# Sch_Rele.net
KiCad netlist of a schematic drawn in Altium Designer
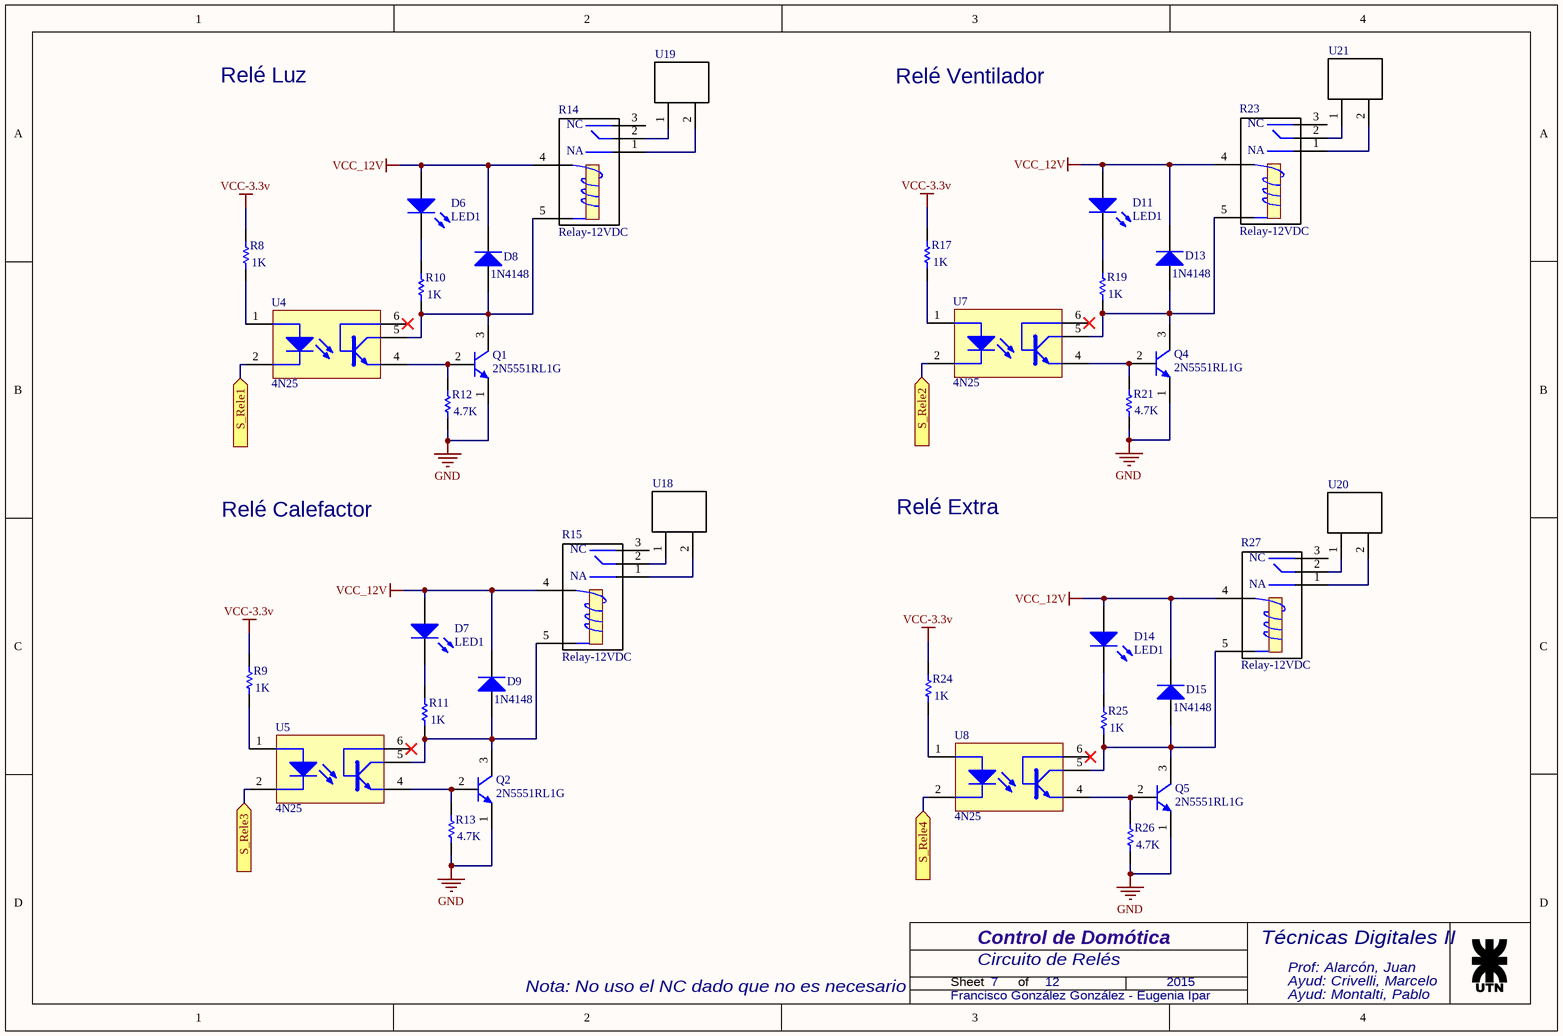
[diagram p0: Sch_Rele.SchDoc]

(export (version "E")
  (design (tool "Eeschema 10.0.6"))
  (components
    (comp (ref "D6")
      (value "LED1")
      (footprint "Type 3mm")
      (description "THT LED round mono-color color lens, WL-TMRW, Super Red")
      (fields (field (name "PARTNUMBER") "151031SS06000") (field (name "MANUFACTURER") "Wuerth Elektronik"))
      (libsource (lib "Altium Content Vault") (part "WE-LED_K1A2-2"))
    )
    (comp (ref "D7")
      (value "LED1")
      (footprint "Type 3mm")
      (description "THT LED round mono-color color lens, WL-TMRW, Super Red")
      (fields (field (name "PARTNUMBER") "151031SS06000") (field (name "MANUFACTURER") "Wuerth Elektronik"))
      (libsource (lib "Altium Content Vault") (part "WE-LED_K1A2-2"))
    )
    (comp (ref "D8")
      (value "1N4148")
      (footprint "DO-35")
      (description "High Conductance Fast Diode")
      (fields (field (name "PUBLISHER") "Altium Limited"))
      (libsource (lib "Miscellaneous Devices") (part "Diode 1N4148"))
    )
    (comp (ref "D9")
      (value "1N4148")
      (footprint "DO-35")
      (description "High Conductance Fast Diode")
      (fields (field (name "PUBLISHER") "Altium Limited"))
      (libsource (lib "Miscellaneous Devices") (part "Diode 1N4148"))
    )
    (comp (ref "D11")
      (value "LED1")
      (footprint "Type 3mm")
      (description "THT LED round mono-color color lens, WL-TMRW, Super Red")
      (fields (field (name "PARTNUMBER") "151031SS06000") (field (name "MANUFACTURER") "Wuerth Elektronik"))
      (libsource (lib "Altium Content Vault") (part "WE-LED_K1A2-2"))
    )
    (comp (ref "D13")
      (value "1N4148")
      (footprint "DO-35")
      (description "High Conductance Fast Diode")
      (fields (field (name "PUBLISHER") "Altium Limited"))
      (libsource (lib "Miscellaneous Devices") (part "Diode 1N4148"))
    )
    (comp (ref "D14")
      (value "LED1")
      (footprint "Type 3mm")
      (description "THT LED round mono-color color lens, WL-TMRW, Super Red")
      (fields (field (name "PARTNUMBER") "151031SS06000") (field (name "MANUFACTURER") "Wuerth Elektronik"))
      (libsource (lib "Altium Content Vault") (part "WE-LED_K1A2-2"))
    )
    (comp (ref "D15")
      (value "1N4148")
      (footprint "DO-35")
      (description "High Conductance Fast Diode")
      (fields (field (name "PUBLISHER") "Altium Limited"))
      (libsource (lib "Miscellaneous Devices") (part "Diode 1N4148"))
    )
    (comp (ref "Q1")
      (value "2N5551RL1G")
      (footprint "ONSC-TO-92-3-29-11_AM_BL")
      (description "Amplifier Transistor, NPN Silicon, 3-Pin TO-92, Pb-Free, Tape and Reel")
      (fields (field (name "MANUFACTURER") "On Semiconductor"))
      (libsource (lib "Altium Content Vault") (part "ONSC-NPN-E1B2C3-3"))
    )
    (comp (ref "Q2")
      (value "2N5551RL1G")
      (footprint "ONSC-TO-92-3-29-11_AM_BL")
      (description "Amplifier Transistor, NPN Silicon, 3-Pin TO-92, Pb-Free, Tape and Reel")
      (fields (field (name "MANUFACTURER") "On Semiconductor"))
      (libsource (lib "Altium Content Vault") (part "ONSC-NPN-E1B2C3-3"))
    )
    (comp (ref "Q4")
      (value "2N5551RL1G")
      (footprint "ONSC-TO-92-3-29-11_AM_BL")
      (description "Amplifier Transistor, NPN Silicon, 3-Pin TO-92, Pb-Free, Tape and Reel")
      (fields (field (name "MANUFACTURER") "On Semiconductor"))
      (libsource (lib "Altium Content Vault") (part "ONSC-NPN-E1B2C3-3"))
    )
    (comp (ref "Q5")
      (value "2N5551RL1G")
      (footprint "ONSC-TO-92-3-29-11_AM_BL")
      (description "Amplifier Transistor, NPN Silicon, 3-Pin TO-92, Pb-Free, Tape and Reel")
      (fields (field (name "MANUFACTURER") "On Semiconductor"))
      (libsource (lib "Altium Content Vault") (part "ONSC-NPN-E1B2C3-3"))
    )
    (comp (ref "R8")
      (value "1K")
      (footprint "AXIAL-0.3")
      (description "Resistor")
      (fields (field (name "Comment") "Res1") (field (name "PUBLISHER") "Altium Limited"))
      (libsource (lib "Miscellaneous Devices") (part "Res1"))
    )
    (comp (ref "R9")
      (value "1K")
      (footprint "AXIAL-0.3")
      (description "Resistor")
      (fields (field (name "Comment") "Res1") (field (name "PUBLISHER") "Altium Limited"))
      (libsource (lib "Miscellaneous Devices") (part "Res1"))
    )
    (comp (ref "R10")
      (value "1K")
      (footprint "AXIAL-0.3")
      (description "Resistor")
      (fields (field (name "Comment") "Res1") (field (name "PUBLISHER") "Altium Limited"))
      (libsource (lib "Miscellaneous Devices") (part "Res1"))
    )
    (comp (ref "R11")
      (value "1K")
      (footprint "AXIAL-0.3")
      (description "Resistor")
      (fields (field (name "Comment") "Res1") (field (name "PUBLISHER") "Altium Limited"))
      (libsource (lib "Miscellaneous Devices") (part "Res1"))
    )
    (comp (ref "R12")
      (value "4.7K")
      (footprint "AXIAL-0.3")
      (description "Resistor")
      (fields (field (name "Comment") "Res1") (field (name "PUBLISHER") "Altium Limited"))
      (libsource (lib "Miscellaneous Devices") (part "Res1"))
    )
    (comp (ref "R13")
      (value "4.7K")
      (footprint "AXIAL-0.3")
      (description "Resistor")
      (fields (field (name "Comment") "Res1") (field (name "PUBLISHER") "Altium Limited"))
      (libsource (lib "Miscellaneous Devices") (part "Res1"))
    )
    (comp (ref "R14") (value "Relay-12VDC") (footprint "Rele") (libsource (lib "") (part "Component_1_1")))
    (comp (ref "R15") (value "Relay-12VDC") (footprint "Rele") (libsource (lib "") (part "Component_1_2")))
    (comp (ref "R17")
      (value "1K")
      (footprint "AXIAL-0.3")
      (description "Resistor")
      (fields (field (name "Comment") "Res1") (field (name "PUBLISHER") "Altium Limited"))
      (libsource (lib "Miscellaneous Devices") (part "Res1"))
    )
    (comp (ref "R19")
      (value "1K")
      (footprint "AXIAL-0.3")
      (description "Resistor")
      (fields (field (name "Comment") "Res1") (field (name "PUBLISHER") "Altium Limited"))
      (libsource (lib "Miscellaneous Devices") (part "Res1"))
    )
    (comp (ref "R21")
      (value "4.7K")
      (footprint "AXIAL-0.3")
      (description "Resistor")
      (fields (field (name "Comment") "Res1") (field (name "PUBLISHER") "Altium Limited"))
      (libsource (lib "Miscellaneous Devices") (part "Res1"))
    )
    (comp (ref "R23")
      (value "Relay-12VDC")
      (footprint "Rele")
      (libsource (lib "Sch_Rele") (part "Component_1"))
    )
    (comp (ref "R24")
      (value "1K")
      (footprint "AXIAL-0.3")
      (description "Resistor")
      (fields (field (name "Comment") "Res1") (field (name "PUBLISHER") "Altium Limited"))
      (libsource (lib "Miscellaneous Devices") (part "Res1"))
    )
    (comp (ref "R25")
      (value "1K")
      (footprint "AXIAL-0.3")
      (description "Resistor")
      (fields (field (name "Comment") "Res1") (field (name "PUBLISHER") "Altium Limited"))
      (libsource (lib "Miscellaneous Devices") (part "Res1"))
    )
    (comp (ref "R26")
      (value "4.7K")
      (footprint "AXIAL-0.3")
      (description "Resistor")
      (fields (field (name "Comment") "Res1") (field (name "PUBLISHER") "Altium Limited"))
      (libsource (lib "Miscellaneous Devices") (part "Res1"))
    )
    (comp (ref "R27") (value "Relay-12VDC") (footprint "Rele") (libsource (lib "") (part "Component_1_2")))
    (comp (ref "U4")
      (value "4N25")
      (footprint "DIP6")
      (description "Optoacoplador")
      (libsource (lib "Sch_Opto") (part "Opto-4N25"))
    )
    (comp (ref "U5")
      (value "4N25")
      (footprint "DIP6")
      (description "Optoacoplador")
      (libsource (lib "Sch_Opto") (part "Opto-4N25"))
    )
    (comp (ref "U7")
      (value "4N25")
      (footprint "DIP6")
      (description "Optoacoplador")
      (libsource (lib "Sch_Opto") (part "Opto-4N25"))
    )
    (comp (ref "U8")
      (value "4N25")
      (footprint "DIP6")
      (description "Optoacoplador")
      (libsource (lib "Sch_Opto") (part "Opto-4N25"))
    )
    (comp (ref "U18")
      (value "Bornera_2P")
      (footprint "Bornera")
      (libsource (lib "Ampli_Lib_Sch") (part "Bornera_2P"))
    )
    (comp (ref "U19")
      (value "Bornera_2P")
      (footprint "Bornera")
      (libsource (lib "Ampli_Lib_Sch") (part "Bornera_2P"))
    )
    (comp (ref "U20")
      (value "Bornera_2P")
      (footprint "Bornera")
      (libsource (lib "Ampli_Lib_Sch") (part "Bornera_2P"))
    )
    (comp (ref "U21")
      (value "Bornera_2P")
      (footprint "Bornera")
      (libsource (lib "Ampli_Lib_Sch") (part "Bornera_2P"))
    )
  )
  (nets
    (net (code "1") (name "/S_Rele1") (class "Default")
      (node (ref "U4") (pin "2") (pinfunction "2_2") (pintype "passive"))
    )
    (net (code "2") (name "/S_Rele2") (class "Default")
      (node (ref "U7") (pin "2") (pinfunction "2_2") (pintype "passive"))
    )
    (net (code "3") (name "/S_Rele3") (class "Default")
      (node (ref "U5") (pin "2") (pinfunction "2_2") (pintype "passive"))
    )
    (net (code "4") (name "/S_Rele4") (class "Default")
      (node (ref "U8") (pin "2") (pinfunction "2_2") (pintype "passive"))
    )
    (net (code "5") (name "GND") (class "Default")
      (node (ref "Q1") (pin "1") (pinfunction "E_1") (pintype "passive"))
      (node (ref "Q2") (pin "1") (pinfunction "E_1") (pintype "passive"))
      (node (ref "Q4") (pin "1") (pinfunction "E_1") (pintype "passive"))
      (node (ref "Q5") (pin "1") (pinfunction "E_1") (pintype "passive"))
      (node (ref "R12") (pin "1") (pinfunction "1_1") (pintype "passive"))
      (node (ref "R13") (pin "1") (pinfunction "1_1") (pintype "passive"))
      (node (ref "R21") (pin "1") (pinfunction "1_1") (pintype "passive"))
      (node (ref "R26") (pin "1") (pinfunction "1_1") (pintype "passive"))
    )
    (net (code "6") (name "Net-(D6-K)") (class "Default")
      (node (ref "D6") (pin "1") (pinfunction "K_1") (pintype "passive"))
      (node (ref "R10") (pin "2") (pinfunction "2_2") (pintype "passive"))
    )
    (net (code "7") (name "Net-(D7-K)") (class "Default")
      (node (ref "D7") (pin "1") (pinfunction "K_1") (pintype "passive"))
      (node (ref "R11") (pin "2") (pinfunction "2_2") (pintype "passive"))
    )
    (net (code "8") (name "Net-(D8-A)") (class "Default")
      (node (ref "D8") (pin "1") (pinfunction "A_1") (pintype "passive"))
      (node (ref "Q1") (pin "3") (pinfunction "C_3") (pintype "passive"))
      (node (ref "R10") (pin "1") (pinfunction "1_1") (pintype "passive"))
      (node (ref "R14") (pin "5") (pinfunction "5_5") (pintype "passive"))
      (node (ref "U4") (pin "5") (pinfunction "5_5") (pintype "passive"))
    )
    (net (code "9") (name "Net-(D9-A)") (class "Default")
      (node (ref "D9") (pin "1") (pinfunction "A_1") (pintype "passive"))
      (node (ref "Q2") (pin "3") (pinfunction "C_3") (pintype "passive"))
      (node (ref "R11") (pin "1") (pinfunction "1_1") (pintype "passive"))
      (node (ref "R15") (pin "5") (pinfunction "5_5") (pintype "passive"))
      (node (ref "U5") (pin "5") (pinfunction "5_5") (pintype "passive"))
    )
    (net (code "10") (name "Net-(D11-K)") (class "Default")
      (node (ref "D11") (pin "1") (pinfunction "K_1") (pintype "passive"))
      (node (ref "R19") (pin "2") (pinfunction "2_2") (pintype "passive"))
    )
    (net (code "11") (name "Net-(D13-A)") (class "Default")
      (node (ref "D13") (pin "1") (pinfunction "A_1") (pintype "passive"))
      (node (ref "Q4") (pin "3") (pinfunction "C_3") (pintype "passive"))
      (node (ref "R19") (pin "1") (pinfunction "1_1") (pintype "passive"))
      (node (ref "R23") (pin "5") (pinfunction "5_5") (pintype "passive"))
      (node (ref "U7") (pin "5") (pinfunction "5_5") (pintype "passive"))
    )
    (net (code "12") (name "Net-(D14-K)") (class "Default")
      (node (ref "D14") (pin "1") (pinfunction "K_1") (pintype "passive"))
      (node (ref "R25") (pin "2") (pinfunction "2_2") (pintype "passive"))
    )
    (net (code "13") (name "Net-(D15-A)") (class "Default")
      (node (ref "D15") (pin "1") (pinfunction "A_1") (pintype "passive"))
      (node (ref "Q5") (pin "3") (pinfunction "C_3") (pintype "passive"))
      (node (ref "R25") (pin "1") (pinfunction "1_1") (pintype "passive"))
      (node (ref "R27") (pin "5") (pinfunction "5_5") (pintype "passive"))
      (node (ref "U8") (pin "5") (pinfunction "5_5") (pintype "passive"))
    )
    (net (code "14") (name "Net-(Q1-B)") (class "Default")
      (node (ref "Q1") (pin "2") (pinfunction "B_2") (pintype "passive"))
      (node (ref "R12") (pin "2") (pinfunction "2_2") (pintype "passive"))
      (node (ref "U4") (pin "4") (pinfunction "4_4") (pintype "passive"))
    )
    (net (code "15") (name "Net-(Q2-B)") (class "Default")
      (node (ref "Q2") (pin "2") (pinfunction "B_2") (pintype "passive"))
      (node (ref "R13") (pin "2") (pinfunction "2_2") (pintype "passive"))
      (node (ref "U5") (pin "4") (pinfunction "4_4") (pintype "passive"))
    )
    (net (code "16") (name "Net-(Q4-B)") (class "Default")
      (node (ref "Q4") (pin "2") (pinfunction "B_2") (pintype "passive"))
      (node (ref "R21") (pin "2") (pinfunction "2_2") (pintype "passive"))
      (node (ref "U7") (pin "4") (pinfunction "4_4") (pintype "passive"))
    )
    (net (code "17") (name "Net-(Q5-B)") (class "Default")
      (node (ref "Q5") (pin "2") (pinfunction "B_2") (pintype "passive"))
      (node (ref "R26") (pin "2") (pinfunction "2_2") (pintype "passive"))
      (node (ref "U8") (pin "4") (pinfunction "4_4") (pintype "passive"))
    )
    (net (code "18") (name "Net-(R8-Pad1)") (class "Default")
      (node (ref "R8") (pin "1") (pinfunction "1_1") (pintype "passive"))
      (node (ref "U4") (pin "1") (pinfunction "1_1") (pintype "passive"))
    )
    (net (code "19") (name "Net-(R9-Pad1)") (class "Default")
      (node (ref "R9") (pin "1") (pinfunction "1_1") (pintype "passive"))
      (node (ref "U5") (pin "1") (pinfunction "1_1") (pintype "passive"))
    )
    (net (code "20") (name "Net-(R14-Pad1)") (class "Default")
      (node (ref "R14") (pin "1") (pinfunction "1_1") (pintype "passive"))
      (node (ref "U19") (pin "2") (pinfunction "2_2") (pintype "passive"))
    )
    (net (code "21") (name "Net-(R14-Pad2)") (class "Default")
      (node (ref "R14") (pin "2") (pinfunction "2_2") (pintype "passive"))
      (node (ref "U19") (pin "1") (pinfunction "1_1") (pintype "passive"))
    )
    (net (code "22") (name "Net-(R15-Pad1)") (class "Default")
      (node (ref "R15") (pin "1") (pinfunction "1_1") (pintype "passive"))
      (node (ref "U18") (pin "2") (pinfunction "2_2") (pintype "passive"))
    )
    (net (code "23") (name "Net-(R15-Pad2)") (class "Default")
      (node (ref "R15") (pin "2") (pinfunction "2_2") (pintype "passive"))
      (node (ref "U18") (pin "1") (pinfunction "1_1") (pintype "passive"))
    )
    (net (code "24") (name "Net-(R17-Pad1)") (class "Default")
      (node (ref "R17") (pin "1") (pinfunction "1_1") (pintype "passive"))
      (node (ref "U7") (pin "1") (pinfunction "1_1") (pintype "passive"))
    )
    (net (code "25") (name "Net-(R23-Pad1)") (class "Default")
      (node (ref "R23") (pin "1") (pinfunction "1_1") (pintype "passive"))
      (node (ref "U21") (pin "2") (pinfunction "2_2") (pintype "passive"))
    )
    (net (code "26") (name "Net-(R23-Pad2)") (class "Default")
      (node (ref "R23") (pin "2") (pinfunction "2_2") (pintype "passive"))
      (node (ref "U21") (pin "1") (pinfunction "1_1") (pintype "passive"))
    )
    (net (code "27") (name "Net-(R24-Pad1)") (class "Default")
      (node (ref "R24") (pin "1") (pinfunction "1_1") (pintype "passive"))
      (node (ref "U8") (pin "1") (pinfunction "1_1") (pintype "passive"))
    )
    (net (code "28") (name "Net-(R27-Pad1)") (class "Default")
      (node (ref "R27") (pin "1") (pinfunction "1_1") (pintype "passive"))
      (node (ref "U20") (pin "2") (pinfunction "2_2") (pintype "passive"))
    )
    (net (code "29") (name "Net-(R27-Pad2)") (class "Default")
      (node (ref "R27") (pin "2") (pinfunction "2_2") (pintype "passive"))
      (node (ref "U20") (pin "1") (pinfunction "1_1") (pintype "passive"))
    )
    (net (code "30") (name "VCC-3.3v") (class "Default")
      (node (ref "R17") (pin "2") (pinfunction "2_2") (pintype "passive"))
      (node (ref "R24") (pin "2") (pinfunction "2_2") (pintype "passive"))
      (node (ref "R8") (pin "2") (pinfunction "2_2") (pintype "passive"))
      (node (ref "R9") (pin "2") (pinfunction "2_2") (pintype "passive"))
    )
    (net (code "31") (name "VCC_12V") (class "Default")
      (node (ref "D11") (pin "2") (pinfunction "A_2") (pintype "passive"))
      (node (ref "D13") (pin "2") (pinfunction "K_2") (pintype "passive"))
      (node (ref "D14") (pin "2") (pinfunction "A_2") (pintype "passive"))
      (node (ref "D15") (pin "2") (pinfunction "K_2") (pintype "passive"))
      (node (ref "D6") (pin "2") (pinfunction "A_2") (pintype "passive"))
      (node (ref "D7") (pin "2") (pinfunction "A_2") (pintype "passive"))
      (node (ref "D8") (pin "2") (pinfunction "K_2") (pintype "passive"))
      (node (ref "D9") (pin "2") (pinfunction "K_2") (pintype "passive"))
      (node (ref "R14") (pin "4") (pinfunction "4_4") (pintype "passive"))
      (node (ref "R15") (pin "4") (pinfunction "4_4") (pintype "passive"))
      (node (ref "R23") (pin "4") (pinfunction "4_4") (pintype "passive"))
      (node (ref "R27") (pin "4") (pinfunction "4_4") (pintype "passive"))
    )
    (net (code "32") (name "unconnected-(R14-Pad3)") (class "Default")
      (node (ref "R14") (pin "3") (pinfunction "3_3") (pintype "passive"))
    )
    (net (code "33") (name "unconnected-(R15-Pad3)") (class "Default")
      (node (ref "R15") (pin "3") (pinfunction "3_3") (pintype "passive"))
    )
    (net (code "34") (name "unconnected-(R23-Pad3)") (class "Default")
      (node (ref "R23") (pin "3") (pinfunction "3_3") (pintype "passive"))
    )
    (net (code "35") (name "unconnected-(R27-Pad3)") (class "Default")
      (node (ref "R27") (pin "3") (pinfunction "3_3") (pintype "passive"))
    )
    (net (code "36") (name "unconnected-(U4-Pad6)") (class "Default")
      (node (ref "U4") (pin "6") (pinfunction "6_6") (pintype "passive+no_connect"))
    )
    (net (code "37") (name "unconnected-(U5-Pad6)") (class "Default")
      (node (ref "U5") (pin "6") (pinfunction "6_6") (pintype "passive+no_connect"))
    )
    (net (code "38") (name "unconnected-(U7-Pad6)") (class "Default")
      (node (ref "U7") (pin "6") (pinfunction "6_6") (pintype "passive+no_connect"))
    )
    (net (code "39") (name "unconnected-(U8-Pad6)") (class "Default")
      (node (ref "U8") (pin "6") (pinfunction "6_6") (pintype "passive+no_connect"))
    )
  )
)
